# PWM_READER.net
KiCad netlist of a schematic drawn in EAGLE
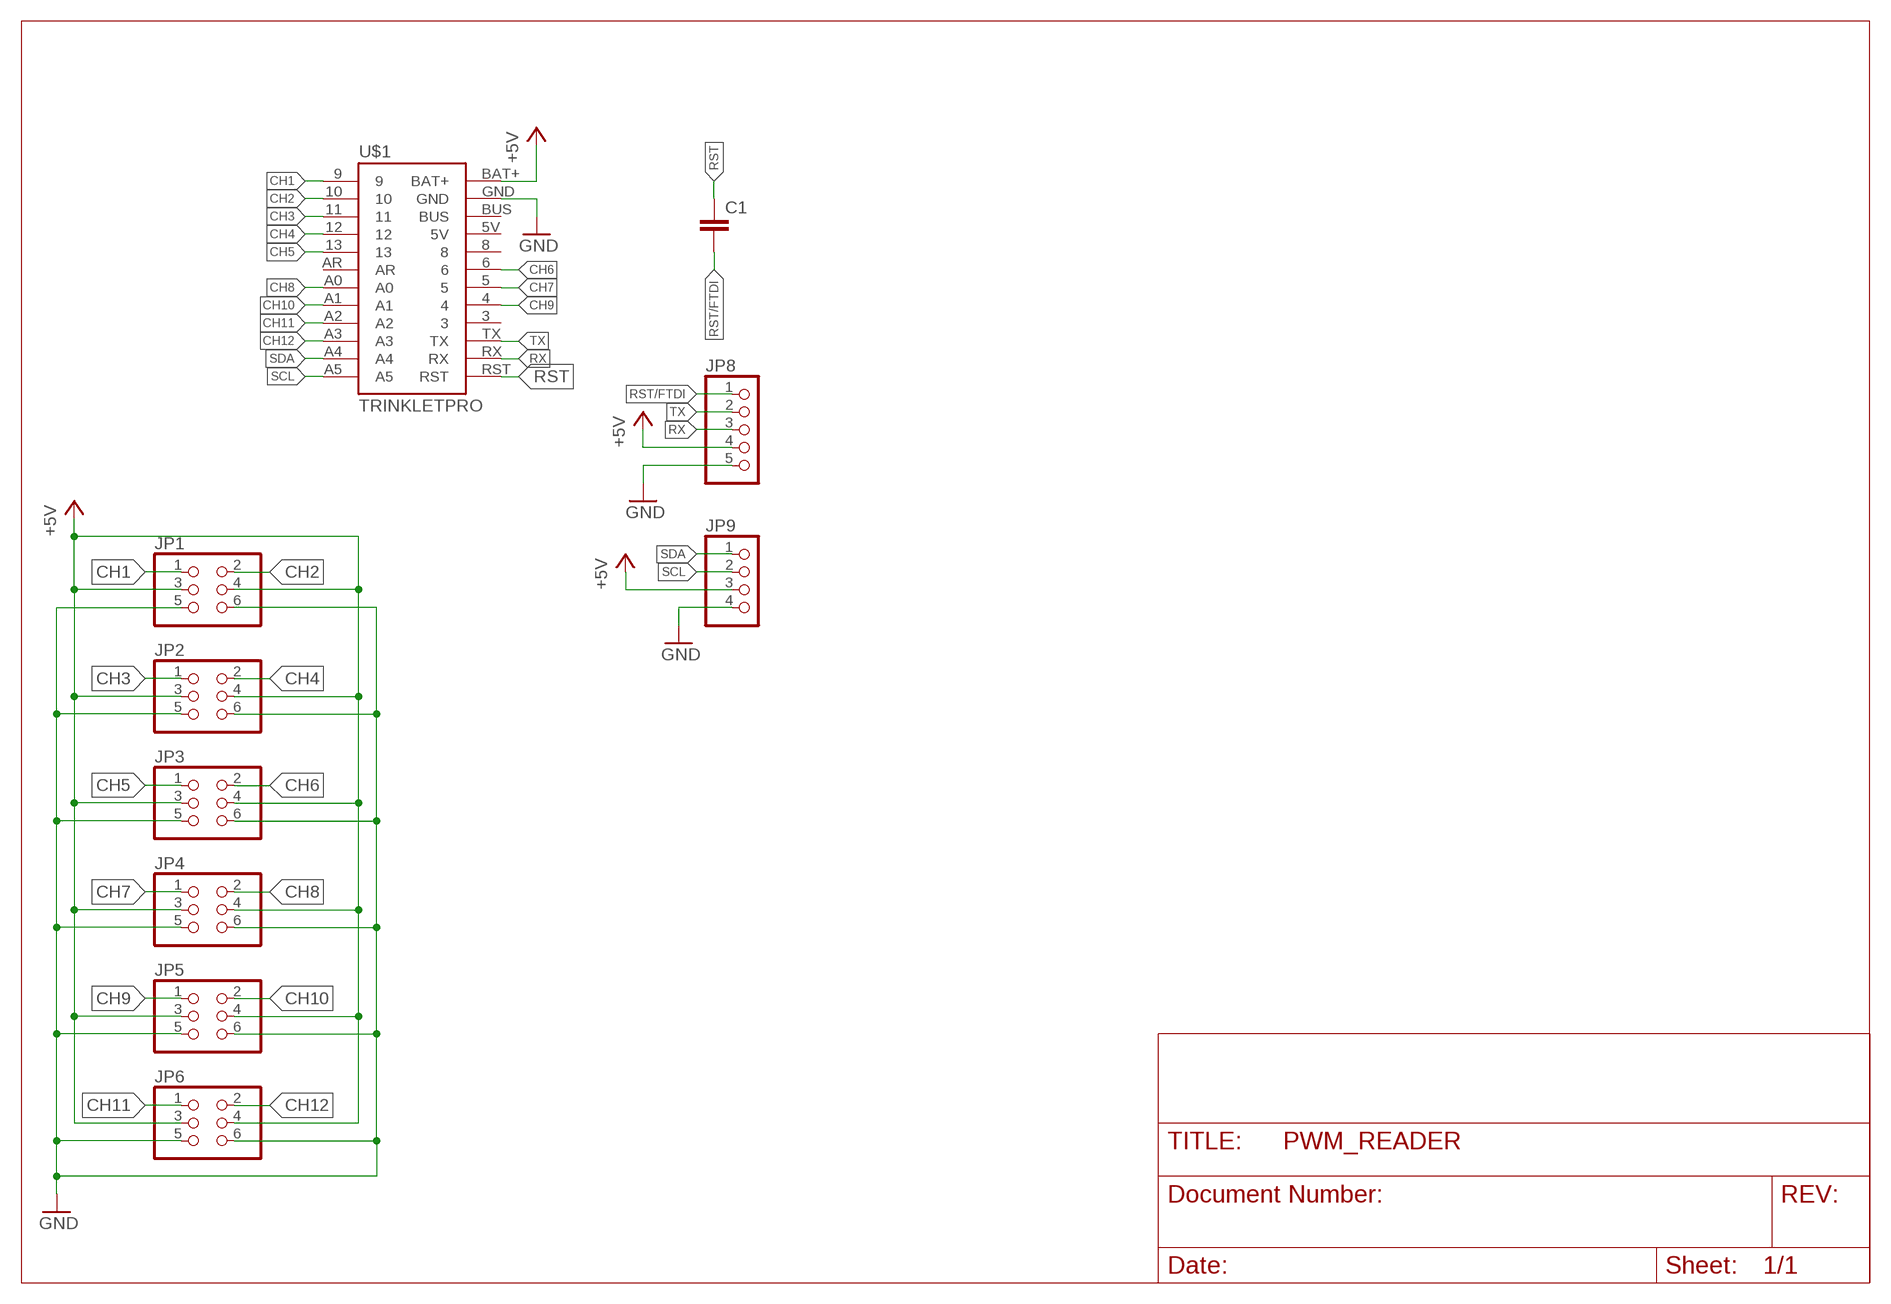
[diagram p0: schematic, sheet 1]

(export (version "E")
  (design (tool "Eeschema 10.0.6"))
  (components
    (comp (ref "C1")
      (value "C-EUC0805")
      (footprint "eagle-import:C0805")
      (libsource (lib "eagle-import") (part "C-EUC0805"))
    )
    (comp (ref "JP1")
      (value "PINHD-2X3")
      (footprint "eagle-import:2X03")
      (libsource (lib "eagle-import") (part "PINHD-2X3"))
    )
    (comp (ref "JP2")
      (value "PINHD-2X3")
      (footprint "eagle-import:2X03")
      (libsource (lib "eagle-import") (part "PINHD-2X3"))
    )
    (comp (ref "JP3")
      (value "PINHD-2X3")
      (footprint "eagle-import:2X03")
      (libsource (lib "eagle-import") (part "PINHD-2X3"))
    )
    (comp (ref "JP4")
      (value "PINHD-2X3")
      (footprint "eagle-import:2X03")
      (libsource (lib "eagle-import") (part "PINHD-2X3"))
    )
    (comp (ref "JP5")
      (value "PINHD-2X3")
      (footprint "eagle-import:2X03")
      (libsource (lib "eagle-import") (part "PINHD-2X3"))
    )
    (comp (ref "JP6")
      (value "PINHD-2X3")
      (footprint "eagle-import:2X03")
      (libsource (lib "eagle-import") (part "PINHD-2X3"))
    )
    (comp (ref "JP8")
      (value "PINHD-1X5")
      (footprint "eagle-import:1X05")
      (libsource (lib "eagle-import") (part "PINHD-1X5"))
    )
    (comp (ref "JP9")
      (value "PINHD-1X4")
      (footprint "eagle-import:1X04")
      (libsource (lib "eagle-import") (part "PINHD-1X4"))
    )
    (comp (ref "U$1")
      (value "TRINKLETPRO")
      (footprint "eagle-import:1X12")
      (libsource (lib "eagle-import") (part "TRINKLETPRO"))
    )
  )
  (nets
    (net (code "1") (name "+5V") (class "Default")
      (node (ref "JP1") (pin "3") (pinfunction "3_3") (pintype "passive"))
      (node (ref "JP1") (pin "4") (pinfunction "4_4") (pintype "passive"))
      (node (ref "JP2") (pin "3") (pinfunction "3_3") (pintype "passive"))
      (node (ref "JP2") (pin "4") (pinfunction "4_4") (pintype "passive"))
      (node (ref "JP3") (pin "3") (pinfunction "3_3") (pintype "passive"))
      (node (ref "JP3") (pin "4") (pinfunction "4_4") (pintype "passive"))
      (node (ref "JP4") (pin "3") (pinfunction "3_3") (pintype "passive"))
      (node (ref "JP4") (pin "4") (pinfunction "4_4") (pintype "passive"))
      (node (ref "JP5") (pin "3") (pinfunction "3_3") (pintype "passive"))
      (node (ref "JP5") (pin "4") (pinfunction "4_4") (pintype "passive"))
      (node (ref "JP6") (pin "3") (pinfunction "3_3") (pintype "passive"))
      (node (ref "JP6") (pin "4") (pinfunction "4_4") (pintype "passive"))
      (node (ref "JP8") (pin "4") (pinfunction "4_4") (pintype "passive"))
      (node (ref "JP9") (pin "3") (pinfunction "3_3") (pintype "passive"))
      (node (ref "U$1") (pin "BAT+") (pinfunction "BAT+_BAT+") (pintype "bidirectional"))
    )
    (net (code "2") (name "CH1") (class "Default")
      (node (ref "JP1") (pin "1") (pinfunction "1_1") (pintype "passive"))
      (node (ref "U$1") (pin "9") (pinfunction "9_9") (pintype "bidirectional"))
    )
    (net (code "3") (name "CH2") (class "Default")
      (node (ref "JP1") (pin "2") (pinfunction "2_2") (pintype "passive"))
      (node (ref "U$1") (pin "10") (pinfunction "10_10") (pintype "bidirectional"))
    )
    (net (code "4") (name "CH3") (class "Default")
      (node (ref "JP2") (pin "1") (pinfunction "1_1") (pintype "passive"))
      (node (ref "U$1") (pin "11") (pinfunction "11_11") (pintype "bidirectional"))
    )
    (net (code "5") (name "CH4") (class "Default")
      (node (ref "JP2") (pin "2") (pinfunction "2_2") (pintype "passive"))
      (node (ref "U$1") (pin "12") (pinfunction "12_12") (pintype "bidirectional"))
    )
    (net (code "6") (name "CH5") (class "Default")
      (node (ref "JP3") (pin "1") (pinfunction "1_1") (pintype "passive"))
      (node (ref "U$1") (pin "13") (pinfunction "13_13") (pintype "bidirectional"))
    )
    (net (code "7") (name "CH6") (class "Default")
      (node (ref "JP3") (pin "2") (pinfunction "2_2") (pintype "passive"))
      (node (ref "U$1") (pin "6") (pinfunction "6_6") (pintype "bidirectional"))
    )
    (net (code "8") (name "CH7") (class "Default")
      (node (ref "JP4") (pin "1") (pinfunction "1_1") (pintype "passive"))
      (node (ref "U$1") (pin "5") (pinfunction "5_5") (pintype "bidirectional"))
    )
    (net (code "9") (name "CH8") (class "Default")
      (node (ref "JP4") (pin "2") (pinfunction "2_2") (pintype "passive"))
      (node (ref "U$1") (pin "A0") (pinfunction "A0_A0") (pintype "bidirectional"))
    )
    (net (code "10") (name "CH9") (class "Default")
      (node (ref "JP5") (pin "1") (pinfunction "1_1") (pintype "passive"))
      (node (ref "U$1") (pin "4") (pinfunction "4_4") (pintype "bidirectional"))
    )
    (net (code "11") (name "CH10") (class "Default")
      (node (ref "JP5") (pin "2") (pinfunction "2_2") (pintype "passive"))
      (node (ref "U$1") (pin "A1") (pinfunction "A1_A1") (pintype "bidirectional"))
    )
    (net (code "12") (name "CH11") (class "Default")
      (node (ref "JP6") (pin "1") (pinfunction "1_1") (pintype "passive"))
      (node (ref "U$1") (pin "A2") (pinfunction "A2_A2") (pintype "bidirectional"))
    )
    (net (code "13") (name "CH12") (class "Default")
      (node (ref "JP6") (pin "2") (pinfunction "2_2") (pintype "passive"))
      (node (ref "U$1") (pin "A3") (pinfunction "A3_A3") (pintype "bidirectional"))
    )
    (net (code "14") (name "GND") (class "Default")
      (node (ref "JP1") (pin "5") (pinfunction "5_5") (pintype "passive"))
      (node (ref "JP1") (pin "6") (pinfunction "6_6") (pintype "passive"))
      (node (ref "JP2") (pin "5") (pinfunction "5_5") (pintype "passive"))
      (node (ref "JP2") (pin "6") (pinfunction "6_6") (pintype "passive"))
      (node (ref "JP3") (pin "5") (pinfunction "5_5") (pintype "passive"))
      (node (ref "JP3") (pin "6") (pinfunction "6_6") (pintype "passive"))
      (node (ref "JP4") (pin "5") (pinfunction "5_5") (pintype "passive"))
      (node (ref "JP4") (pin "6") (pinfunction "6_6") (pintype "passive"))
      (node (ref "JP5") (pin "5") (pinfunction "5_5") (pintype "passive"))
      (node (ref "JP5") (pin "6") (pinfunction "6_6") (pintype "passive"))
      (node (ref "JP6") (pin "5") (pinfunction "5_5") (pintype "passive"))
      (node (ref "JP6") (pin "6") (pinfunction "6_6") (pintype "passive"))
      (node (ref "JP8") (pin "5") (pinfunction "5_5") (pintype "passive"))
      (node (ref "JP9") (pin "4") (pinfunction "4_4") (pintype "passive"))
      (node (ref "U$1") (pin "GND") (pinfunction "GND_GND") (pintype "bidirectional"))
    )
    (net (code "15") (name "RST") (class "Default")
      (node (ref "C1") (pin "1") (pinfunction "1_1") (pintype "passive"))
      (node (ref "U$1") (pin "RST") (pinfunction "RST_RST") (pintype "bidirectional"))
    )
    (net (code "16") (name "RST{slash}FTDI") (class "Default")
      (node (ref "C1") (pin "2") (pinfunction "2_2") (pintype "passive"))
      (node (ref "JP8") (pin "1") (pinfunction "1_1") (pintype "passive"))
    )
    (net (code "17") (name "RX") (class "Default")
      (node (ref "JP8") (pin "3") (pinfunction "3_3") (pintype "passive"))
      (node (ref "U$1") (pin "RX") (pinfunction "RX_RX") (pintype "bidirectional"))
    )
    (net (code "18") (name "SCL") (class "Default")
      (node (ref "JP9") (pin "2") (pinfunction "2_2") (pintype "passive"))
      (node (ref "U$1") (pin "A5") (pinfunction "A5_A5") (pintype "bidirectional"))
    )
    (net (code "19") (name "SDA") (class "Default")
      (node (ref "JP9") (pin "1") (pinfunction "1_1") (pintype "passive"))
      (node (ref "U$1") (pin "A4") (pinfunction "A4_A4") (pintype "bidirectional"))
    )
    (net (code "20") (name "TX") (class "Default")
      (node (ref "JP8") (pin "2") (pinfunction "2_2") (pintype "passive"))
      (node (ref "U$1") (pin "TX") (pinfunction "TX_TX") (pintype "bidirectional"))
    )
    (net (code "21") (name "unconnected-(U$1-Pad3)") (class "Default")
      (node (ref "U$1") (pin "3") (pinfunction "3_3") (pintype "bidirectional"))
    )
    (net (code "22") (name "unconnected-(U$1-Pad5V)") (class "Default")
      (node (ref "U$1") (pin "5V") (pinfunction "5V_5V") (pintype "bidirectional"))
    )
    (net (code "23") (name "unconnected-(U$1-Pad8)") (class "Default")
      (node (ref "U$1") (pin "8") (pinfunction "8_8") (pintype "bidirectional"))
    )
    (net (code "24") (name "unconnected-(U$1-PadAR)") (class "Default")
      (node (ref "U$1") (pin "AR") (pinfunction "AR_AR") (pintype "bidirectional"))
    )
    (net (code "25") (name "unconnected-(U$1-PadBUS)") (class "Default")
      (node (ref "U$1") (pin "BUS") (pinfunction "BUS_BUS") (pintype "bidirectional"))
    )
  )
)
